# 02-MIC.net
KiCad netlist of a schematic drawn in Altium Designer
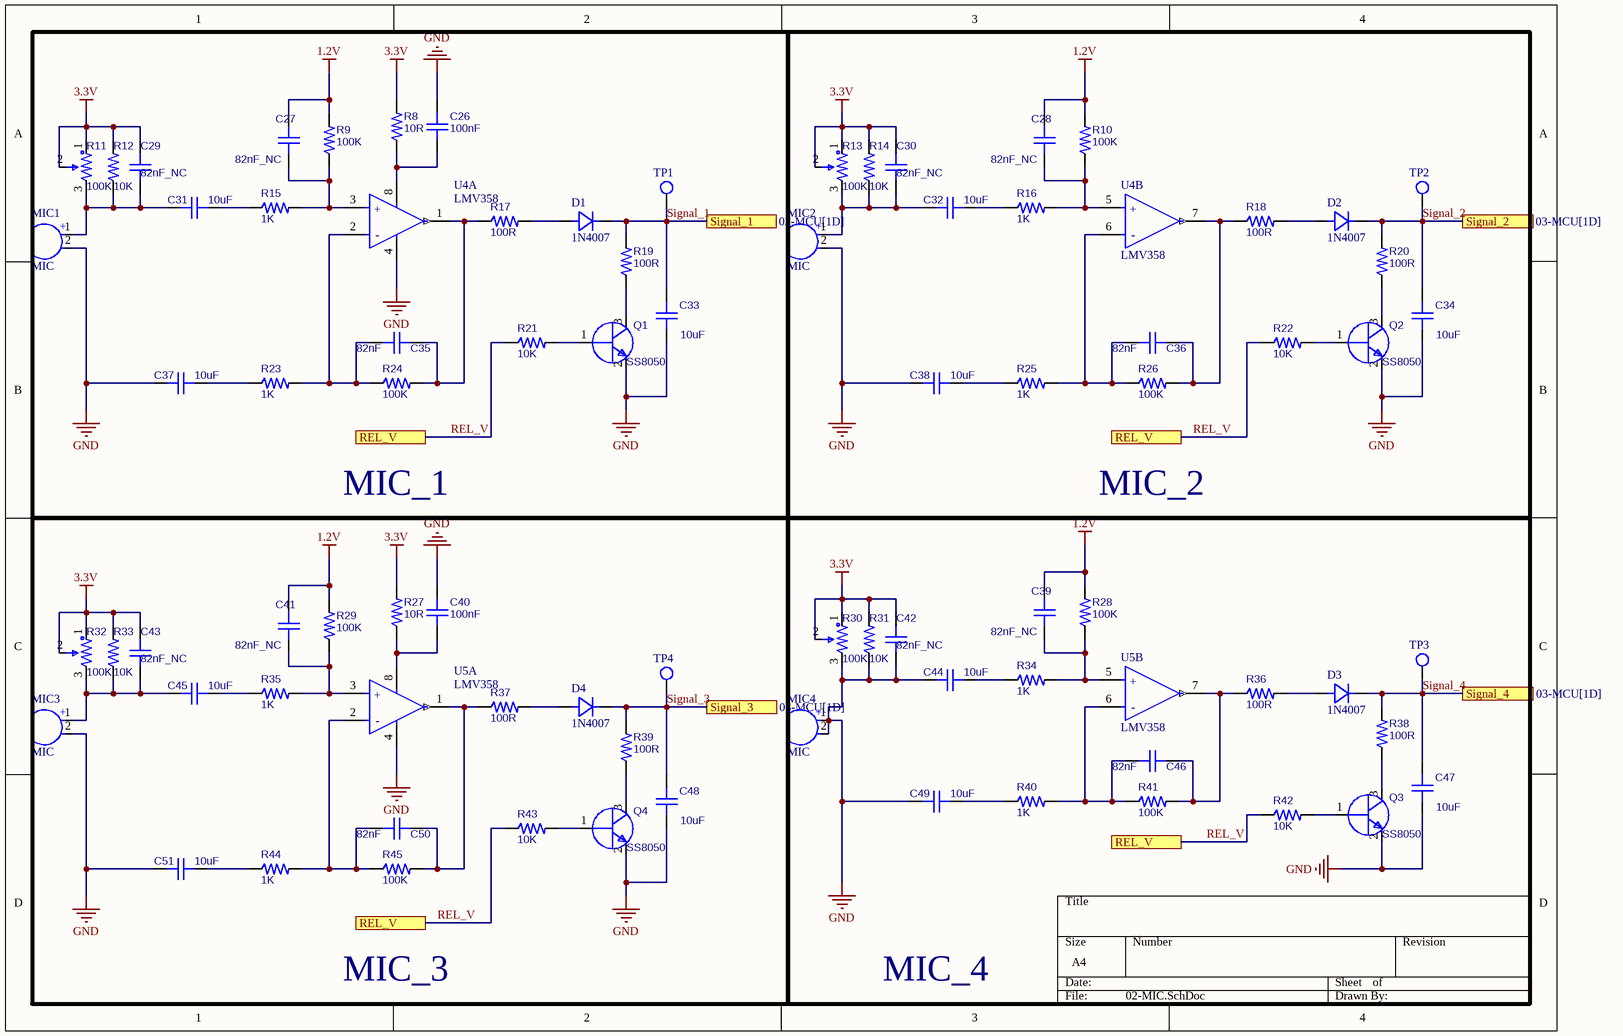
[diagram p0: 02-MIC.SchDoc]

(export (version "E")
  (design (tool "Eeschema 10.0.6"))
  (components
    (comp (ref "C26")
      (value "100nF")
      (footprint "CAP-SMD-0603")
      (description "贴片电容")
      (fields
        (field (name "BOM_MANUFACTURER PART") "CL03A104KQ3NNNC")
        (field (name "BOM_SUPPLIER PART") "C160831")
        (field (name "CONTRIBUTOR") "LCSC")
      )
      (libsource (lib "声源跟踪小车原理图库") (part "CAP"))
    )
    (comp (ref "C27")
      (value "82nF_NC")
      (footprint "CAP-SMD-0603")
      (description "贴片电容")
      (fields
        (field (name "BOM_MANUFACTURER PART") "CL03A104KQ3NNNC")
        (field (name "BOM_SUPPLIER PART") "C160831")
        (field (name "CONTRIBUTOR") "LCSC")
      )
      (libsource (lib "声源跟踪小车原理图库") (part "CAP"))
    )
    (comp (ref "C28")
      (value "82nF_NC")
      (footprint "CAP-SMD-0603")
      (description "贴片电容")
      (fields
        (field (name "BOM_MANUFACTURER PART") "CL03A104KQ3NNNC")
        (field (name "BOM_SUPPLIER PART") "C160831")
        (field (name "CONTRIBUTOR") "LCSC")
      )
      (libsource (lib "声源跟踪小车原理图库") (part "CAP"))
    )
    (comp (ref "C29")
      (value "82nF_NC")
      (footprint "CAP-SMD-0603")
      (description "贴片电容")
      (fields
        (field (name "BOM_MANUFACTURER PART") "CL03A104KQ3NNNC")
        (field (name "BOM_SUPPLIER PART") "C160831")
        (field (name "CONTRIBUTOR") "LCSC")
      )
      (libsource (lib "声源跟踪小车原理图库") (part "CAP"))
    )
    (comp (ref "C30")
      (value "82nF_NC")
      (footprint "CAP-SMD-0603")
      (description "贴片电容")
      (fields
        (field (name "BOM_MANUFACTURER PART") "CL03A104KQ3NNNC")
        (field (name "BOM_SUPPLIER PART") "C160831")
        (field (name "CONTRIBUTOR") "LCSC")
      )
      (libsource (lib "声源跟踪小车原理图库") (part "CAP"))
    )
    (comp (ref "C31")
      (value "10uF")
      (footprint "CAP-SMD-0603")
      (description "贴片电容")
      (fields
        (field (name "BOM_MANUFACTURER PART") "CL03A104KQ3NNNC")
        (field (name "BOM_SUPPLIER PART") "C160831")
        (field (name "CONTRIBUTOR") "LCSC")
      )
      (libsource (lib "声源跟踪小车原理图库") (part "CAP"))
    )
    (comp (ref "C32")
      (value "10uF")
      (footprint "CAP-SMD-0603")
      (description "贴片电容")
      (fields
        (field (name "BOM_MANUFACTURER PART") "CL03A104KQ3NNNC")
        (field (name "BOM_SUPPLIER PART") "C160831")
        (field (name "CONTRIBUTOR") "LCSC")
      )
      (libsource (lib "声源跟踪小车原理图库") (part "CAP"))
    )
    (comp (ref "C33")
      (value "10uF")
      (footprint "CAP-SMD-0603")
      (description "贴片电容")
      (fields
        (field (name "BOM_MANUFACTURER PART") "CL03A104KQ3NNNC")
        (field (name "BOM_SUPPLIER PART") "C160831")
        (field (name "CONTRIBUTOR") "LCSC")
      )
      (libsource (lib "声源跟踪小车原理图库") (part "CAP"))
    )
    (comp (ref "C34")
      (value "10uF")
      (footprint "CAP-SMD-0603")
      (description "贴片电容")
      (fields
        (field (name "BOM_MANUFACTURER PART") "CL03A104KQ3NNNC")
        (field (name "BOM_SUPPLIER PART") "C160831")
        (field (name "CONTRIBUTOR") "LCSC")
      )
      (libsource (lib "声源跟踪小车原理图库") (part "CAP"))
    )
    (comp (ref "C35")
      (value "82nF")
      (footprint "CAP-SMD-0603")
      (description "贴片电容")
      (fields
        (field (name "BOM_MANUFACTURER PART") "CL03A104KQ3NNNC")
        (field (name "BOM_SUPPLIER PART") "C160831")
        (field (name "CONTRIBUTOR") "LCSC")
      )
      (libsource (lib "声源跟踪小车原理图库") (part "CAP"))
    )
    (comp (ref "C36")
      (value "82nF")
      (footprint "CAP-SMD-0603")
      (description "贴片电容")
      (fields
        (field (name "BOM_MANUFACTURER PART") "CL03A104KQ3NNNC")
        (field (name "BOM_SUPPLIER PART") "C160831")
        (field (name "CONTRIBUTOR") "LCSC")
      )
      (libsource (lib "声源跟踪小车原理图库") (part "CAP"))
    )
    (comp (ref "C37")
      (value "10uF")
      (footprint "CAP-SMD-0603")
      (description "贴片电容")
      (fields
        (field (name "BOM_MANUFACTURER PART") "CL03A104KQ3NNNC")
        (field (name "BOM_SUPPLIER PART") "C160831")
        (field (name "CONTRIBUTOR") "LCSC")
      )
      (libsource (lib "声源跟踪小车原理图库") (part "CAP"))
    )
    (comp (ref "C38")
      (value "10uF")
      (footprint "CAP-SMD-0603")
      (description "贴片电容")
      (fields
        (field (name "BOM_MANUFACTURER PART") "CL03A104KQ3NNNC")
        (field (name "BOM_SUPPLIER PART") "C160831")
        (field (name "CONTRIBUTOR") "LCSC")
      )
      (libsource (lib "声源跟踪小车原理图库") (part "CAP"))
    )
    (comp (ref "C39")
      (value "82nF_NC")
      (footprint "CAP-SMD-0603")
      (description "贴片电容")
      (fields
        (field (name "BOM_MANUFACTURER PART") "CL03A104KQ3NNNC")
        (field (name "BOM_SUPPLIER PART") "C160831")
        (field (name "CONTRIBUTOR") "LCSC")
      )
      (libsource (lib "声源跟踪小车原理图库") (part "CAP"))
    )
    (comp (ref "C40")
      (value "100nF")
      (footprint "CAP-SMD-0603")
      (description "贴片电容")
      (fields
        (field (name "BOM_MANUFACTURER PART") "CL03A104KQ3NNNC")
        (field (name "BOM_SUPPLIER PART") "C160831")
        (field (name "CONTRIBUTOR") "LCSC")
      )
      (libsource (lib "声源跟踪小车原理图库") (part "CAP"))
    )
    (comp (ref "C41")
      (value "82nF_NC")
      (footprint "CAP-SMD-0603")
      (description "贴片电容")
      (fields
        (field (name "BOM_MANUFACTURER PART") "CL03A104KQ3NNNC")
        (field (name "BOM_SUPPLIER PART") "C160831")
        (field (name "CONTRIBUTOR") "LCSC")
      )
      (libsource (lib "声源跟踪小车原理图库") (part "CAP"))
    )
    (comp (ref "C42")
      (value "82nF_NC")
      (footprint "CAP-SMD-0603")
      (description "贴片电容")
      (fields
        (field (name "BOM_MANUFACTURER PART") "CL03A104KQ3NNNC")
        (field (name "BOM_SUPPLIER PART") "C160831")
        (field (name "CONTRIBUTOR") "LCSC")
      )
      (libsource (lib "声源跟踪小车原理图库") (part "CAP"))
    )
    (comp (ref "C43")
      (value "82nF_NC")
      (footprint "CAP-SMD-0603")
      (description "贴片电容")
      (fields
        (field (name "BOM_MANUFACTURER PART") "CL03A104KQ3NNNC")
        (field (name "BOM_SUPPLIER PART") "C160831")
        (field (name "CONTRIBUTOR") "LCSC")
      )
      (libsource (lib "声源跟踪小车原理图库") (part "CAP"))
    )
    (comp (ref "C44")
      (value "10uF")
      (footprint "CAP-SMD-0603")
      (description "贴片电容")
      (fields
        (field (name "BOM_MANUFACTURER PART") "CL03A104KQ3NNNC")
        (field (name "BOM_SUPPLIER PART") "C160831")
        (field (name "CONTRIBUTOR") "LCSC")
      )
      (libsource (lib "声源跟踪小车原理图库") (part "CAP"))
    )
    (comp (ref "C45")
      (value "10uF")
      (footprint "CAP-SMD-0603")
      (description "贴片电容")
      (fields
        (field (name "BOM_MANUFACTURER PART") "CL03A104KQ3NNNC")
        (field (name "BOM_SUPPLIER PART") "C160831")
        (field (name "CONTRIBUTOR") "LCSC")
      )
      (libsource (lib "声源跟踪小车原理图库") (part "CAP"))
    )
    (comp (ref "C46")
      (value "82nF")
      (footprint "CAP-SMD-0603")
      (description "贴片电容")
      (fields
        (field (name "BOM_MANUFACTURER PART") "CL03A104KQ3NNNC")
        (field (name "BOM_SUPPLIER PART") "C160831")
        (field (name "CONTRIBUTOR") "LCSC")
      )
      (libsource (lib "声源跟踪小车原理图库") (part "CAP"))
    )
    (comp (ref "C47")
      (value "10uF")
      (footprint "CAP-SMD-0603")
      (description "贴片电容")
      (fields
        (field (name "BOM_MANUFACTURER PART") "CL03A104KQ3NNNC")
        (field (name "BOM_SUPPLIER PART") "C160831")
        (field (name "CONTRIBUTOR") "LCSC")
      )
      (libsource (lib "声源跟踪小车原理图库") (part "CAP"))
    )
    (comp (ref "C48")
      (value "10uF")
      (footprint "CAP-SMD-0603")
      (description "贴片电容")
      (fields
        (field (name "BOM_MANUFACTURER PART") "CL03A104KQ3NNNC")
        (field (name "BOM_SUPPLIER PART") "C160831")
        (field (name "CONTRIBUTOR") "LCSC")
      )
      (libsource (lib "声源跟踪小车原理图库") (part "CAP"))
    )
    (comp (ref "C49")
      (value "10uF")
      (footprint "CAP-SMD-0603")
      (description "贴片电容")
      (fields
        (field (name "BOM_MANUFACTURER PART") "CL03A104KQ3NNNC")
        (field (name "BOM_SUPPLIER PART") "C160831")
        (field (name "CONTRIBUTOR") "LCSC")
      )
      (libsource (lib "声源跟踪小车原理图库") (part "CAP"))
    )
    (comp (ref "C50")
      (value "82nF")
      (footprint "CAP-SMD-0603")
      (description "贴片电容")
      (fields
        (field (name "BOM_MANUFACTURER PART") "CL03A104KQ3NNNC")
        (field (name "BOM_SUPPLIER PART") "C160831")
        (field (name "CONTRIBUTOR") "LCSC")
      )
      (libsource (lib "声源跟踪小车原理图库") (part "CAP"))
    )
    (comp (ref "C51")
      (value "10uF")
      (footprint "CAP-SMD-0603")
      (description "贴片电容")
      (fields
        (field (name "BOM_MANUFACTURER PART") "CL03A104KQ3NNNC")
        (field (name "BOM_SUPPLIER PART") "C160831")
        (field (name "CONTRIBUTOR") "LCSC")
      )
      (libsource (lib "声源跟踪小车原理图库") (part "CAP"))
    )
    (comp (ref "D1")
      (value "1N4007")
      (footprint "SOD-123-P3.4")
      (description "二极管1N4148W")
      (fields (field (name "MANUFACTURER") "PSI(宝力芯)") (field (name "MANUFACTURER PART") "1N4148W"))
      (libsource (lib "声源跟踪小车原理图库") (part "Diode"))
    )
    (comp (ref "D2")
      (value "1N4007")
      (footprint "SOD-123-P3.4")
      (description "二极管1N4148W")
      (fields (field (name "MANUFACTURER") "PSI(宝力芯)") (field (name "MANUFACTURER PART") "1N4148W"))
      (libsource (lib "声源跟踪小车原理图库") (part "Diode"))
    )
    (comp (ref "D3")
      (value "1N4007")
      (footprint "SOD-123-P3.4")
      (description "二极管1N4148W")
      (fields (field (name "MANUFACTURER") "PSI(宝力芯)") (field (name "MANUFACTURER PART") "1N4148W"))
      (libsource (lib "声源跟踪小车原理图库") (part "Diode"))
    )
    (comp (ref "D4")
      (value "1N4007")
      (footprint "SOD-123-P3.4")
      (description "二极管1N4148W")
      (fields (field (name "MANUFACTURER") "PSI(宝力芯)") (field (name "MANUFACTURER PART") "1N4148W"))
      (libsource (lib "声源跟踪小车原理图库") (part "Diode"))
    )
    (comp (ref "MIC1")
      (value "MIC")
      (footprint "CONN-TH-1X2P-P2.54_2")
      (description "咪头MIC COND ANALOG OMNI -38DB")
      (libsource (lib "声源跟踪小车原理图库") (part "MIC"))
    )
    (comp (ref "MIC2")
      (value "MIC")
      (footprint "CONN-TH-1X2P-P2.54_2")
      (description "咪头MIC COND ANALOG OMNI -38DB")
      (libsource (lib "声源跟踪小车原理图库") (part "MIC"))
    )
    (comp (ref "MIC3")
      (value "MIC")
      (footprint "CONN-TH-1X2P-P2.54_2")
      (description "咪头MIC COND ANALOG OMNI -38DB")
      (libsource (lib "声源跟踪小车原理图库") (part "MIC"))
    )
    (comp (ref "MIC4")
      (value "MIC")
      (footprint "CONN-TH-1X2P-P2.54_2")
      (description "咪头MIC COND ANALOG OMNI -38DB")
      (libsource (lib "声源跟踪小车原理图库") (part "MIC"))
    )
    (comp (ref "Q1")
      (value "SS8050")
      (footprint "SOT-23-3-LP2.28-P1.91")
      (description "贴片NPN三极管")
      (fields
        (field (name "BOM_SUPPLIER PART") "C2898668")
        (field (name "BOM_MANUFACTURER PART") "S9013")
        (field (name "CONTRIBUTOR") "LCSC")
      )
      (libsource (lib "声源跟踪小车原理图库") (part "NPN-SOT-23-3"))
    )
    (comp (ref "Q2")
      (value "SS8050")
      (footprint "SOT-23-3-LP2.28-P1.91")
      (description "贴片NPN三极管")
      (fields
        (field (name "BOM_SUPPLIER PART") "C2898668")
        (field (name "BOM_MANUFACTURER PART") "S9013")
        (field (name "CONTRIBUTOR") "LCSC")
      )
      (libsource (lib "声源跟踪小车原理图库") (part "NPN-SOT-23-3"))
    )
    (comp (ref "Q3")
      (value "SS8050")
      (footprint "SOT-23-3-LP2.28-P1.91")
      (description "贴片NPN三极管")
      (fields
        (field (name "BOM_SUPPLIER PART") "C2898668")
        (field (name "BOM_MANUFACTURER PART") "S9013")
        (field (name "CONTRIBUTOR") "LCSC")
      )
      (libsource (lib "声源跟踪小车原理图库") (part "NPN-SOT-23-3"))
    )
    (comp (ref "Q4")
      (value "SS8050")
      (footprint "SOT-23-3-LP2.28-P1.91")
      (description "贴片NPN三极管")
      (fields
        (field (name "BOM_SUPPLIER PART") "C2898668")
        (field (name "BOM_MANUFACTURER PART") "S9013")
        (field (name "CONTRIBUTOR") "LCSC")
      )
      (libsource (lib "声源跟踪小车原理图库") (part "NPN-SOT-23-3"))
    )
    (comp (ref "R8")
      (value "10R")
      (footprint "RES-SMD-0603")
      (description "贴片电阻")
      (fields
        (field (name "BOM_SUPPLIER PART") "C118966")
        (field (name "BOM_MANUFACTURER PART") "3362P-1-104")
        (field (name "CONTRIBUTOR") "LCSC")
      )
      (libsource (lib "声源跟踪小车原理图库") (part "RES"))
    )
    (comp (ref "R9")
      (value "100K")
      (footprint "RES-SMD-0603")
      (description "贴片电阻")
      (fields
        (field (name "BOM_SUPPLIER PART") "C118966")
        (field (name "BOM_MANUFACTURER PART") "3362P-1-104")
        (field (name "CONTRIBUTOR") "LCSC")
      )
      (libsource (lib "声源跟踪小车原理图库") (part "RES"))
    )
    (comp (ref "R10")
      (value "100K")
      (footprint "RES-SMD-0603")
      (description "贴片电阻")
      (fields
        (field (name "BOM_SUPPLIER PART") "C118966")
        (field (name "BOM_MANUFACTURER PART") "3362P-1-104")
        (field (name "CONTRIBUTOR") "LCSC")
      )
      (libsource (lib "声源跟踪小车原理图库") (part "RES"))
    )
    (comp (ref "R11")
      (value "100K")
      (footprint "RES-TH-ADJ-3396W")
      (description "可调电阻,电位器")
      (fields
        (field (name "BOM_SUPPLIER PART") "C118966")
        (field (name "BOM_MANUFACTURER PART") "3362P-1-104")
        (field (name "CONTRIBUTOR") "LCSC")
      )
      (libsource (lib "声源跟踪小车原理图库") (part "RES-ADJ"))
    )
    (comp (ref "R12")
      (value "10K")
      (footprint "RES-SMD-0603")
      (description "贴片电阻")
      (fields
        (field (name "BOM_SUPPLIER PART") "C118966")
        (field (name "BOM_MANUFACTURER PART") "3362P-1-104")
        (field (name "CONTRIBUTOR") "LCSC")
      )
      (libsource (lib "声源跟踪小车原理图库") (part "RES"))
    )
    (comp (ref "R13")
      (value "100K")
      (footprint "RES-TH-ADJ-3396W")
      (description "可调电阻,电位器")
      (fields
        (field (name "BOM_SUPPLIER PART") "C118966")
        (field (name "BOM_MANUFACTURER PART") "3362P-1-104")
        (field (name "CONTRIBUTOR") "LCSC")
      )
      (libsource (lib "声源跟踪小车原理图库") (part "RES-ADJ"))
    )
    (comp (ref "R14")
      (value "10K")
      (footprint "RES-SMD-0603")
      (description "贴片电阻")
      (fields
        (field (name "BOM_SUPPLIER PART") "C118966")
        (field (name "BOM_MANUFACTURER PART") "3362P-1-104")
        (field (name "CONTRIBUTOR") "LCSC")
      )
      (libsource (lib "声源跟踪小车原理图库") (part "RES"))
    )
    (comp (ref "R15")
      (value "1K")
      (footprint "RES-SMD-0603")
      (description "贴片电阻")
      (fields
        (field (name "BOM_SUPPLIER PART") "C118966")
        (field (name "BOM_MANUFACTURER PART") "3362P-1-104")
        (field (name "CONTRIBUTOR") "LCSC")
      )
      (libsource (lib "声源跟踪小车原理图库") (part "RES"))
    )
    (comp (ref "R16")
      (value "1K")
      (footprint "RES-SMD-0603")
      (description "贴片电阻")
      (fields
        (field (name "BOM_SUPPLIER PART") "C118966")
        (field (name "BOM_MANUFACTURER PART") "3362P-1-104")
        (field (name "CONTRIBUTOR") "LCSC")
      )
      (libsource (lib "声源跟踪小车原理图库") (part "RES"))
    )
    (comp (ref "R17")
      (value "100R")
      (footprint "RES-SMD-0603")
      (description "贴片电阻")
      (fields
        (field (name "BOM_SUPPLIER PART") "C118966")
        (field (name "BOM_MANUFACTURER PART") "3362P-1-104")
        (field (name "CONTRIBUTOR") "LCSC")
      )
      (libsource (lib "声源跟踪小车原理图库") (part "RES"))
    )
    (comp (ref "R18")
      (value "100R")
      (footprint "RES-SMD-0603")
      (description "贴片电阻")
      (fields
        (field (name "BOM_SUPPLIER PART") "C118966")
        (field (name "BOM_MANUFACTURER PART") "3362P-1-104")
        (field (name "CONTRIBUTOR") "LCSC")
      )
      (libsource (lib "声源跟踪小车原理图库") (part "RES"))
    )
    (comp (ref "R19")
      (value "100R")
      (footprint "RES-SMD-0603")
      (description "贴片电阻")
      (fields
        (field (name "BOM_SUPPLIER PART") "C118966")
        (field (name "BOM_MANUFACTURER PART") "3362P-1-104")
        (field (name "CONTRIBUTOR") "LCSC")
      )
      (libsource (lib "声源跟踪小车原理图库") (part "RES"))
    )
    (comp (ref "R20")
      (value "100R")
      (footprint "RES-SMD-0603")
      (description "贴片电阻")
      (fields
        (field (name "BOM_SUPPLIER PART") "C118966")
        (field (name "BOM_MANUFACTURER PART") "3362P-1-104")
        (field (name "CONTRIBUTOR") "LCSC")
      )
      (libsource (lib "声源跟踪小车原理图库") (part "RES"))
    )
    (comp (ref "R21")
      (value "10K")
      (footprint "RES-SMD-0603")
      (description "贴片电阻")
      (fields
        (field (name "BOM_SUPPLIER PART") "C118966")
        (field (name "BOM_MANUFACTURER PART") "3362P-1-104")
        (field (name "CONTRIBUTOR") "LCSC")
      )
      (libsource (lib "声源跟踪小车原理图库") (part "RES"))
    )
    (comp (ref "R22")
      (value "10K")
      (footprint "RES-SMD-0603")
      (description "贴片电阻")
      (fields
        (field (name "BOM_SUPPLIER PART") "C118966")
        (field (name "BOM_MANUFACTURER PART") "3362P-1-104")
        (field (name "CONTRIBUTOR") "LCSC")
      )
      (libsource (lib "声源跟踪小车原理图库") (part "RES"))
    )
    (comp (ref "R23")
      (value "1K")
      (footprint "RES-SMD-0603")
      (description "贴片电阻")
      (fields
        (field (name "BOM_SUPPLIER PART") "C118966")
        (field (name "BOM_MANUFACTURER PART") "3362P-1-104")
        (field (name "CONTRIBUTOR") "LCSC")
      )
      (libsource (lib "声源跟踪小车原理图库") (part "RES"))
    )
    (comp (ref "R24")
      (value "100K")
      (footprint "RES-SMD-0603")
      (description "贴片电阻")
      (fields
        (field (name "BOM_SUPPLIER PART") "C118966")
        (field (name "BOM_MANUFACTURER PART") "3362P-1-104")
        (field (name "CONTRIBUTOR") "LCSC")
      )
      (libsource (lib "声源跟踪小车原理图库") (part "RES"))
    )
    (comp (ref "R25")
      (value "1K")
      (footprint "RES-SMD-0603")
      (description "贴片电阻")
      (fields
        (field (name "BOM_SUPPLIER PART") "C118966")
        (field (name "BOM_MANUFACTURER PART") "3362P-1-104")
        (field (name "CONTRIBUTOR") "LCSC")
      )
      (libsource (lib "声源跟踪小车原理图库") (part "RES"))
    )
    (comp (ref "R26")
      (value "100K")
      (footprint "RES-SMD-0603")
      (description "贴片电阻")
      (fields
        (field (name "BOM_SUPPLIER PART") "C118966")
        (field (name "BOM_MANUFACTURER PART") "3362P-1-104")
        (field (name "CONTRIBUTOR") "LCSC")
      )
      (libsource (lib "声源跟踪小车原理图库") (part "RES"))
    )
    (comp (ref "R27")
      (value "10R")
      (footprint "RES-SMD-0603")
      (description "贴片电阻")
      (fields
        (field (name "BOM_SUPPLIER PART") "C118966")
        (field (name "BOM_MANUFACTURER PART") "3362P-1-104")
        (field (name "CONTRIBUTOR") "LCSC")
      )
      (libsource (lib "声源跟踪小车原理图库") (part "RES"))
    )
    (comp (ref "R28")
      (value "100K")
      (footprint "RES-SMD-0603")
      (description "贴片电阻")
      (fields
        (field (name "BOM_SUPPLIER PART") "C118966")
        (field (name "BOM_MANUFACTURER PART") "3362P-1-104")
        (field (name "CONTRIBUTOR") "LCSC")
      )
      (libsource (lib "声源跟踪小车原理图库") (part "RES"))
    )
    (comp (ref "R29")
      (value "100K")
      (footprint "RES-SMD-0603")
      (description "贴片电阻")
      (fields
        (field (name "BOM_SUPPLIER PART") "C118966")
        (field (name "BOM_MANUFACTURER PART") "3362P-1-104")
        (field (name "CONTRIBUTOR") "LCSC")
      )
      (libsource (lib "声源跟踪小车原理图库") (part "RES"))
    )
    (comp (ref "R30")
      (value "100K")
      (footprint "RES-TH-ADJ-3396W")
      (description "可调电阻,电位器")
      (fields
        (field (name "BOM_SUPPLIER PART") "C118966")
        (field (name "BOM_MANUFACTURER PART") "3362P-1-104")
        (field (name "CONTRIBUTOR") "LCSC")
      )
      (libsource (lib "声源跟踪小车原理图库") (part "RES-ADJ"))
    )
    (comp (ref "R31")
      (value "10K")
      (footprint "RES-SMD-0603")
      (description "贴片电阻")
      (fields
        (field (name "BOM_SUPPLIER PART") "C118966")
        (field (name "BOM_MANUFACTURER PART") "3362P-1-104")
        (field (name "CONTRIBUTOR") "LCSC")
      )
      (libsource (lib "声源跟踪小车原理图库") (part "RES"))
    )
    (comp (ref "R32")
      (value "100K")
      (footprint "RES-TH-ADJ-3396W")
      (description "可调电阻,电位器")
      (fields
        (field (name "BOM_SUPPLIER PART") "C118966")
        (field (name "BOM_MANUFACTURER PART") "3362P-1-104")
        (field (name "CONTRIBUTOR") "LCSC")
      )
      (libsource (lib "声源跟踪小车原理图库") (part "RES-ADJ"))
    )
    (comp (ref "R33")
      (value "10K")
      (footprint "RES-SMD-0603")
      (description "贴片电阻")
      (fields
        (field (name "BOM_SUPPLIER PART") "C118966")
        (field (name "BOM_MANUFACTURER PART") "3362P-1-104")
        (field (name "CONTRIBUTOR") "LCSC")
      )
      (libsource (lib "声源跟踪小车原理图库") (part "RES"))
    )
    (comp (ref "R34")
      (value "1K")
      (footprint "RES-SMD-0603")
      (description "贴片电阻")
      (fields
        (field (name "BOM_SUPPLIER PART") "C118966")
        (field (name "BOM_MANUFACTURER PART") "3362P-1-104")
        (field (name "CONTRIBUTOR") "LCSC")
      )
      (libsource (lib "声源跟踪小车原理图库") (part "RES"))
    )
    (comp (ref "R35")
      (value "1K")
      (footprint "RES-SMD-0603")
      (description "贴片电阻")
      (fields
        (field (name "BOM_SUPPLIER PART") "C118966")
        (field (name "BOM_MANUFACTURER PART") "3362P-1-104")
        (field (name "CONTRIBUTOR") "LCSC")
      )
      (libsource (lib "声源跟踪小车原理图库") (part "RES"))
    )
    (comp (ref "R36")
      (value "100R")
      (footprint "RES-SMD-0603")
      (description "贴片电阻")
      (fields
        (field (name "BOM_SUPPLIER PART") "C118966")
        (field (name "BOM_MANUFACTURER PART") "3362P-1-104")
        (field (name "CONTRIBUTOR") "LCSC")
      )
      (libsource (lib "声源跟踪小车原理图库") (part "RES"))
    )
    (comp (ref "R37")
      (value "100R")
      (footprint "RES-SMD-0603")
      (description "贴片电阻")
      (fields
        (field (name "BOM_SUPPLIER PART") "C118966")
        (field (name "BOM_MANUFACTURER PART") "3362P-1-104")
        (field (name "CONTRIBUTOR") "LCSC")
      )
      (libsource (lib "声源跟踪小车原理图库") (part "RES"))
    )
    (comp (ref "R38")
      (value "100R")
      (footprint "RES-SMD-0603")
      (description "贴片电阻")
      (fields
        (field (name "BOM_SUPPLIER PART") "C118966")
        (field (name "BOM_MANUFACTURER PART") "3362P-1-104")
        (field (name "CONTRIBUTOR") "LCSC")
      )
      (libsource (lib "声源跟踪小车原理图库") (part "RES"))
    )
    (comp (ref "R39")
      (value "100R")
      (footprint "RES-SMD-0603")
      (description "贴片电阻")
      (fields
        (field (name "BOM_SUPPLIER PART") "C118966")
        (field (name "BOM_MANUFACTURER PART") "3362P-1-104")
        (field (name "CONTRIBUTOR") "LCSC")
      )
      (libsource (lib "声源跟踪小车原理图库") (part "RES"))
    )
    (comp (ref "R40")
      (value "1K")
      (footprint "RES-SMD-0603")
      (description "贴片电阻")
      (fields
        (field (name "BOM_SUPPLIER PART") "C118966")
        (field (name "BOM_MANUFACTURER PART") "3362P-1-104")
        (field (name "CONTRIBUTOR") "LCSC")
      )
      (libsource (lib "声源跟踪小车原理图库") (part "RES"))
    )
    (comp (ref "R41")
      (value "100K")
      (footprint "RES-SMD-0603")
      (description "贴片电阻")
      (fields
        (field (name "BOM_SUPPLIER PART") "C118966")
        (field (name "BOM_MANUFACTURER PART") "3362P-1-104")
        (field (name "CONTRIBUTOR") "LCSC")
      )
      (libsource (lib "声源跟踪小车原理图库") (part "RES"))
    )
    (comp (ref "R42")
      (value "10K")
      (footprint "RES-SMD-0603")
      (description "贴片电阻")
      (fields
        (field (name "BOM_SUPPLIER PART") "C118966")
        (field (name "BOM_MANUFACTURER PART") "3362P-1-104")
        (field (name "CONTRIBUTOR") "LCSC")
      )
      (libsource (lib "声源跟踪小车原理图库") (part "RES"))
    )
    (comp (ref "R43")
      (value "10K")
      (footprint "RES-SMD-0603")
      (description "贴片电阻")
      (fields
        (field (name "BOM_SUPPLIER PART") "C118966")
        (field (name "BOM_MANUFACTURER PART") "3362P-1-104")
        (field (name "CONTRIBUTOR") "LCSC")
      )
      (libsource (lib "声源跟踪小车原理图库") (part "RES"))
    )
    (comp (ref "R44")
      (value "1K")
      (footprint "RES-SMD-0603")
      (description "贴片电阻")
      (fields
        (field (name "BOM_SUPPLIER PART") "C118966")
        (field (name "BOM_MANUFACTURER PART") "3362P-1-104")
        (field (name "CONTRIBUTOR") "LCSC")
      )
      (libsource (lib "声源跟踪小车原理图库") (part "RES"))
    )
    (comp (ref "R45")
      (value "100K")
      (footprint "RES-SMD-0603")
      (description "贴片电阻")
      (fields
        (field (name "BOM_SUPPLIER PART") "C118966")
        (field (name "BOM_MANUFACTURER PART") "3362P-1-104")
        (field (name "CONTRIBUTOR") "LCSC")
      )
      (libsource (lib "声源跟踪小车原理图库") (part "RES"))
    )
    (comp (ref "TP1")
      (value "TP")
      (footprint "TP")
      (description "TP测试点")
      (libsource (lib "声源跟踪小车原理图库") (part "TP"))
    )
    (comp (ref "TP2")
      (value "TP")
      (footprint "TP")
      (description "TP测试点")
      (libsource (lib "声源跟踪小车原理图库") (part "TP"))
    )
    (comp (ref "TP3")
      (value "TP")
      (footprint "TP")
      (description "TP测试点")
      (libsource (lib "声源跟踪小车原理图库") (part "TP"))
    )
    (comp (ref "TP4")
      (value "TP")
      (footprint "TP")
      (description "TP测试点")
      (libsource (lib "声源跟踪小车原理图库") (part "TP"))
    )
    (comp (ref "U4")
      (value "LMV358")
      (footprint "SOIC-8-LP5.5-P1.27")
      (description "运放IC OPAMP GP 2 CIRCUIT 8SOIC")
      (libsource (lib "声源跟踪小车原理图库") (part "LMV358"))
    )
    (comp (ref "U5")
      (value "LMV358")
      (footprint "SOIC-8-LP5.5-P1.27")
      (description "运放IC OPAMP GP 2 CIRCUIT 8SOIC")
      (libsource (lib "声源跟踪小车原理图库") (part "LMV358"))
    )
  )
  (nets
    (net (code "1") (name "/REL_V") (class "Default")
      (node (ref "R21") (pin "1") (pinfunction "1_1") (pintype "passive"))
      (node (ref "R22") (pin "1") (pinfunction "1_1") (pintype "passive"))
      (node (ref "R42") (pin "1") (pinfunction "1_1") (pintype "passive"))
      (node (ref "R43") (pin "1") (pinfunction "1_1") (pintype "passive"))
    )
    (net (code "2") (name "/Signal_1") (class "Default")
      (node (ref "C33") (pin "2") (pinfunction "2_2") (pintype "passive"))
      (node (ref "D1") (pin "2") (pinfunction "A_2") (pintype "passive"))
      (node (ref "R19") (pin "2") (pinfunction "2_2") (pintype "passive"))
      (node (ref "TP1") (pin "1") (pinfunction "1_1") (pintype "passive"))
    )
    (net (code "3") (name "/Signal_2") (class "Default")
      (node (ref "C34") (pin "2") (pinfunction "2_2") (pintype "passive"))
      (node (ref "D2") (pin "2") (pinfunction "A_2") (pintype "passive"))
      (node (ref "R20") (pin "2") (pinfunction "2_2") (pintype "passive"))
      (node (ref "TP2") (pin "1") (pinfunction "1_1") (pintype "passive"))
    )
    (net (code "4") (name "/Signal_3") (class "Default")
      (node (ref "C48") (pin "2") (pinfunction "2_2") (pintype "passive"))
      (node (ref "D4") (pin "2") (pinfunction "A_2") (pintype "passive"))
      (node (ref "R39") (pin "2") (pinfunction "2_2") (pintype "passive"))
      (node (ref "TP4") (pin "1") (pinfunction "1_1") (pintype "passive"))
    )
    (net (code "5") (name "/Signal_4") (class "Default")
      (node (ref "C47") (pin "2") (pinfunction "2_2") (pintype "passive"))
      (node (ref "D3") (pin "2") (pinfunction "A_2") (pintype "passive"))
      (node (ref "R38") (pin "2") (pinfunction "2_2") (pintype "passive"))
      (node (ref "TP3") (pin "1") (pinfunction "1_1") (pintype "passive"))
    )
    (net (code "6") (name "1.2V") (class "Default")
      (node (ref "C27") (pin "2") (pinfunction "2_2") (pintype "passive"))
      (node (ref "C28") (pin "2") (pinfunction "2_2") (pintype "passive"))
      (node (ref "C39") (pin "2") (pinfunction "2_2") (pintype "passive"))
      (node (ref "C41") (pin "2") (pinfunction "2_2") (pintype "passive"))
      (node (ref "R10") (pin "2") (pinfunction "2_2") (pintype "passive"))
      (node (ref "R28") (pin "2") (pinfunction "2_2") (pintype "passive"))
      (node (ref "R29") (pin "2") (pinfunction "2_2") (pintype "passive"))
      (node (ref "R9") (pin "2") (pinfunction "2_2") (pintype "passive"))
    )
    (net (code "7") (name "3.3V") (class "Default")
      (node (ref "C29") (pin "2") (pinfunction "2_2") (pintype "passive"))
      (node (ref "C30") (pin "2") (pinfunction "2_2") (pintype "passive"))
      (node (ref "C42") (pin "2") (pinfunction "2_2") (pintype "passive"))
      (node (ref "C43") (pin "2") (pinfunction "2_2") (pintype "passive"))
      (node (ref "R11") (pin "1") (pinfunction "1_1") (pintype "passive"))
      (node (ref "R11") (pin "2") (pinfunction "2_2") (pintype "passive"))
      (node (ref "R12") (pin "2") (pinfunction "2_2") (pintype "passive"))
      (node (ref "R13") (pin "1") (pinfunction "1_1") (pintype "passive"))
      (node (ref "R13") (pin "2") (pinfunction "2_2") (pintype "passive"))
      (node (ref "R14") (pin "2") (pinfunction "2_2") (pintype "passive"))
      (node (ref "R27") (pin "2") (pinfunction "2_2") (pintype "passive"))
      (node (ref "R30") (pin "1") (pinfunction "1_1") (pintype "passive"))
      (node (ref "R30") (pin "2") (pinfunction "2_2") (pintype "passive"))
      (node (ref "R31") (pin "2") (pinfunction "2_2") (pintype "passive"))
      (node (ref "R32") (pin "1") (pinfunction "1_1") (pintype "passive"))
      (node (ref "R32") (pin "2") (pinfunction "2_2") (pintype "passive"))
      (node (ref "R33") (pin "2") (pinfunction "2_2") (pintype "passive"))
      (node (ref "R8") (pin "2") (pinfunction "2_2") (pintype "passive"))
    )
    (net (code "8") (name "GND") (class "Default")
      (node (ref "C26") (pin "2") (pinfunction "2_2") (pintype "passive"))
      (node (ref "C33") (pin "1") (pinfunction "1_1") (pintype "passive"))
      (node (ref "C34") (pin "1") (pinfunction "1_1") (pintype "passive"))
      (node (ref "C37") (pin "1") (pinfunction "1_1") (pintype "passive"))
      (node (ref "C38") (pin "1") (pinfunction "1_1") (pintype "passive"))
      (node (ref "C40") (pin "2") (pinfunction "2_2") (pintype "passive"))
      (node (ref "C42") (pin "1") (pinfunction "1_1") (pintype "passive"))
      (node (ref "C44") (pin "1") (pinfunction "1_1") (pintype "passive"))
      (node (ref "C47") (pin "1") (pinfunction "1_1") (pintype "passive"))
      (node (ref "C48") (pin "1") (pinfunction "1_1") (pintype "passive"))
      (node (ref "C49") (pin "1") (pinfunction "1_1") (pintype "passive"))
      (node (ref "C51") (pin "1") (pinfunction "1_1") (pintype "passive"))
      (node (ref "MIC1") (pin "2") (pinfunction "C_2") (pintype "passive"))
      (node (ref "MIC2") (pin "2") (pinfunction "C_2") (pintype "passive"))
      (node (ref "MIC3") (pin "2") (pinfunction "C_2") (pintype "passive"))
      (node (ref "MIC4") (pin "1") (pinfunction "A_1") (pintype "passive"))
      (node (ref "MIC4") (pin "2") (pinfunction "C_2") (pintype "passive"))
      (node (ref "Q1") (pin "2") (pinfunction "E_2") (pintype "passive"))
      (node (ref "Q2") (pin "2") (pinfunction "E_2") (pintype "passive"))
      (node (ref "Q3") (pin "2") (pinfunction "E_2") (pintype "passive"))
      (node (ref "Q4") (pin "2") (pinfunction "E_2") (pintype "passive"))
      (node (ref "R30") (pin "3") (pinfunction "3_3") (pintype "passive"))
      (node (ref "R31") (pin "1") (pinfunction "1_1") (pintype "passive"))
      (node (ref "U4") (pin "4") (pinfunction "GND_4") (pintype "power_in"))
      (node (ref "U5") (pin "4") (pinfunction "GND_4") (pintype "power_in"))
    )
    (net (code "9") (name "Net-(C31-Pad2)") (class "Default")
      (node (ref "C31") (pin "2") (pinfunction "2_2") (pintype "passive"))
      (node (ref "R15") (pin "1") (pinfunction "1_1") (pintype "passive"))
    )
    (net (code "10") (name "Net-(C32-Pad2)") (class "Default")
      (node (ref "C32") (pin "2") (pinfunction "2_2") (pintype "passive"))
      (node (ref "R16") (pin "1") (pinfunction "1_1") (pintype "passive"))
    )
    (net (code "11") (name "Net-(C37-Pad2)") (class "Default")
      (node (ref "C37") (pin "2") (pinfunction "2_2") (pintype "passive"))
      (node (ref "R23") (pin "1") (pinfunction "1_1") (pintype "passive"))
    )
    (net (code "12") (name "Net-(C38-Pad2)") (class "Default")
      (node (ref "C38") (pin "2") (pinfunction "2_2") (pintype "passive"))
      (node (ref "R25") (pin "1") (pinfunction "1_1") (pintype "passive"))
    )
    (net (code "13") (name "Net-(C44-Pad2)") (class "Default")
      (node (ref "C44") (pin "2") (pinfunction "2_2") (pintype "passive"))
      (node (ref "R34") (pin "1") (pinfunction "1_1") (pintype "passive"))
    )
    (net (code "14") (name "Net-(C45-Pad2)") (class "Default")
      (node (ref "C45") (pin "2") (pinfunction "2_2") (pintype "passive"))
      (node (ref "R35") (pin "1") (pinfunction "1_1") (pintype "passive"))
    )
    (net (code "15") (name "Net-(C49-Pad2)") (class "Default")
      (node (ref "C49") (pin "2") (pinfunction "2_2") (pintype "passive"))
      (node (ref "R40") (pin "1") (pinfunction "1_1") (pintype "passive"))
    )
    (net (code "16") (name "Net-(C51-Pad2)") (class "Default")
      (node (ref "C51") (pin "2") (pinfunction "2_2") (pintype "passive"))
      (node (ref "R44") (pin "1") (pinfunction "1_1") (pintype "passive"))
    )
    (net (code "17") (name "Net-(D1-K)") (class "Default")
      (node (ref "D1") (pin "1") (pinfunction "K_1") (pintype "passive"))
      (node (ref "R17") (pin "2") (pinfunction "2_2") (pintype "passive"))
    )
    (net (code "18") (name "Net-(D2-K)") (class "Default")
      (node (ref "D2") (pin "1") (pinfunction "K_1") (pintype "passive"))
      (node (ref "R18") (pin "2") (pinfunction "2_2") (pintype "passive"))
    )
    (net (code "19") (name "Net-(D3-K)") (class "Default")
      (node (ref "D3") (pin "1") (pinfunction "K_1") (pintype "passive"))
      (node (ref "R36") (pin "2") (pinfunction "2_2") (pintype "passive"))
    )
    (net (code "20") (name "Net-(D4-K)") (class "Default")
      (node (ref "D4") (pin "1") (pinfunction "K_1") (pintype "passive"))
      (node (ref "R37") (pin "2") (pinfunction "2_2") (pintype "passive"))
    )
    (net (code "21") (name "Net-(MIC1-A)") (class "Default")
      (node (ref "C29") (pin "1") (pinfunction "1_1") (pintype "passive"))
      (node (ref "C31") (pin "1") (pinfunction "1_1") (pintype "passive"))
      (node (ref "MIC1") (pin "1") (pinfunction "A_1") (pintype "passive"))
      (node (ref "R11") (pin "3") (pinfunction "3_3") (pintype "passive"))
      (node (ref "R12") (pin "1") (pinfunction "1_1") (pintype "passive"))
    )
    (net (code "22") (name "Net-(MIC2-A)") (class "Default")
      (node (ref "C30") (pin "1") (pinfunction "1_1") (pintype "passive"))
      (node (ref "C32") (pin "1") (pinfunction "1_1") (pintype "passive"))
      (node (ref "MIC2") (pin "1") (pinfunction "A_1") (pintype "passive"))
      (node (ref "R13") (pin "3") (pinfunction "3_3") (pintype "passive"))
      (node (ref "R14") (pin "1") (pinfunction "1_1") (pintype "passive"))
    )
    (net (code "23") (name "Net-(MIC3-A)") (class "Default")
      (node (ref "C43") (pin "1") (pinfunction "1_1") (pintype "passive"))
      (node (ref "C45") (pin "1") (pinfunction "1_1") (pintype "passive"))
      (node (ref "MIC3") (pin "1") (pinfunction "A_1") (pintype "passive"))
      (node (ref "R32") (pin "3") (pinfunction "3_3") (pintype "passive"))
      (node (ref "R33") (pin "1") (pinfunction "1_1") (pintype "passive"))
    )
    (net (code "24") (name "Net-(Q1-B)") (class "Default")
      (node (ref "Q1") (pin "1") (pinfunction "B_1") (pintype "passive"))
      (node (ref "R21") (pin "2") (pinfunction "2_2") (pintype "passive"))
    )
    (net (code "25") (name "Net-(Q1-C)") (class "Default")
      (node (ref "Q1") (pin "3") (pinfunction "C_3") (pintype "passive"))
      (node (ref "R19") (pin "1") (pinfunction "1_1") (pintype "passive"))
    )
    (net (code "26") (name "Net-(Q2-B)") (class "Default")
      (node (ref "Q2") (pin "1") (pinfunction "B_1") (pintype "passive"))
      (node (ref "R22") (pin "2") (pinfunction "2_2") (pintype "passive"))
    )
    (net (code "27") (name "Net-(Q2-C)") (class "Default")
      (node (ref "Q2") (pin "3") (pinfunction "C_3") (pintype "passive"))
      (node (ref "R20") (pin "1") (pinfunction "1_1") (pintype "passive"))
    )
    (net (code "28") (name "Net-(Q3-B)") (class "Default")
      (node (ref "Q3") (pin "1") (pinfunction "B_1") (pintype "passive"))
      (node (ref "R42") (pin "2") (pinfunction "2_2") (pintype "passive"))
    )
    (net (code "29") (name "Net-(Q3-C)") (class "Default")
      (node (ref "Q3") (pin "3") (pinfunction "C_3") (pintype "passive"))
      (node (ref "R38") (pin "1") (pinfunction "1_1") (pintype "passive"))
    )
    (net (code "30") (name "Net-(Q4-B)") (class "Default")
      (node (ref "Q4") (pin "1") (pinfunction "B_1") (pintype "passive"))
      (node (ref "R43") (pin "2") (pinfunction "2_2") (pintype "passive"))
    )
    (net (code "31") (name "Net-(Q4-C)") (class "Default")
      (node (ref "Q4") (pin "3") (pinfunction "C_3") (pintype "passive"))
      (node (ref "R39") (pin "1") (pinfunction "1_1") (pintype "passive"))
    )
    (net (code "32") (name "Net-(U4A-1IN+)") (class "Default")
      (node (ref "C27") (pin "1") (pinfunction "1_1") (pintype "passive"))
      (node (ref "R15") (pin "2") (pinfunction "2_2") (pintype "passive"))
      (node (ref "R9") (pin "1") (pinfunction "1_1") (pintype "passive"))
      (node (ref "U4") (pin "3") (pinfunction "1IN+_3") (pintype "tri_state"))
    )
    (net (code "33") (name "Net-(U4A-1IN-)") (class "Default")
      (node (ref "C35") (pin "1") (pinfunction "1_1") (pintype "passive"))
      (node (ref "R23") (pin "2") (pinfunction "2_2") (pintype "passive"))
      (node (ref "R24") (pin "1") (pinfunction "1_1") (pintype "passive"))
      (node (ref "U4") (pin "2") (pinfunction "1IN-_2") (pintype "tri_state"))
    )
    (net (code "34") (name "Net-(U4A-OUT)") (class "Default")
      (node (ref "C35") (pin "2") (pinfunction "2_2") (pintype "passive"))
      (node (ref "R17") (pin "1") (pinfunction "1_1") (pintype "passive"))
      (node (ref "R24") (pin "2") (pinfunction "2_2") (pintype "passive"))
      (node (ref "U4") (pin "1") (pinfunction "OUT_1") (pintype "output"))
    )
    (net (code "35") (name "Net-(U4A-VCC+)") (class "Default")
      (node (ref "C26") (pin "1") (pinfunction "1_1") (pintype "passive"))
      (node (ref "R8") (pin "1") (pinfunction "1_1") (pintype "passive"))
      (node (ref "U4") (pin "8") (pinfunction "VCC+_8") (pintype "power_in"))
    )
    (net (code "36") (name "Net-(U4B-1IN+)") (class "Default")
      (node (ref "C28") (pin "1") (pinfunction "1_1") (pintype "passive"))
      (node (ref "R10") (pin "1") (pinfunction "1_1") (pintype "passive"))
      (node (ref "R16") (pin "2") (pinfunction "2_2") (pintype "passive"))
      (node (ref "U4") (pin "5") (pinfunction "1IN+_5") (pintype "tri_state"))
    )
    (net (code "37") (name "Net-(U4B-1IN-)") (class "Default")
      (node (ref "C36") (pin "1") (pinfunction "1_1") (pintype "passive"))
      (node (ref "R25") (pin "2") (pinfunction "2_2") (pintype "passive"))
      (node (ref "R26") (pin "1") (pinfunction "1_1") (pintype "passive"))
      (node (ref "U4") (pin "6") (pinfunction "1IN-_6") (pintype "tri_state"))
    )
    (net (code "38") (name "Net-(U4B-OUT)") (class "Default")
      (node (ref "C36") (pin "2") (pinfunction "2_2") (pintype "passive"))
      (node (ref "R18") (pin "1") (pinfunction "1_1") (pintype "passive"))
      (node (ref "R26") (pin "2") (pinfunction "2_2") (pintype "passive"))
      (node (ref "U4") (pin "7") (pinfunction "OUT_7") (pintype "output"))
    )
    (net (code "39") (name "Net-(U5A-1IN+)") (class "Default")
      (node (ref "C41") (pin "1") (pinfunction "1_1") (pintype "passive"))
      (node (ref "R29") (pin "1") (pinfunction "1_1") (pintype "passive"))
      (node (ref "R35") (pin "2") (pinfunction "2_2") (pintype "passive"))
      (node (ref "U5") (pin "3") (pinfunction "1IN+_3") (pintype "tri_state"))
    )
    (net (code "40") (name "Net-(U5A-1IN-)") (class "Default")
      (node (ref "C50") (pin "1") (pinfunction "1_1") (pintype "passive"))
      (node (ref "R44") (pin "2") (pinfunction "2_2") (pintype "passive"))
      (node (ref "R45") (pin "1") (pinfunction "1_1") (pintype "passive"))
      (node (ref "U5") (pin "2") (pinfunction "1IN-_2") (pintype "tri_state"))
    )
    (net (code "41") (name "Net-(U5A-OUT)") (class "Default")
      (node (ref "C50") (pin "2") (pinfunction "2_2") (pintype "passive"))
      (node (ref "R37") (pin "1") (pinfunction "1_1") (pintype "passive"))
      (node (ref "R45") (pin "2") (pinfunction "2_2") (pintype "passive"))
      (node (ref "U5") (pin "1") (pinfunction "OUT_1") (pintype "output"))
    )
    (net (code "42") (name "Net-(U5A-VCC+)") (class "Default")
      (node (ref "C40") (pin "1") (pinfunction "1_1") (pintype "passive"))
      (node (ref "R27") (pin "1") (pinfunction "1_1") (pintype "passive"))
      (node (ref "U5") (pin "8") (pinfunction "VCC+_8") (pintype "power_in"))
    )
    (net (code "43") (name "Net-(U5B-1IN+)") (class "Default")
      (node (ref "C39") (pin "1") (pinfunction "1_1") (pintype "passive"))
      (node (ref "R28") (pin "1") (pinfunction "1_1") (pintype "passive"))
      (node (ref "R34") (pin "2") (pinfunction "2_2") (pintype "passive"))
      (node (ref "U5") (pin "5") (pinfunction "1IN+_5") (pintype "tri_state"))
    )
    (net (code "44") (name "Net-(U5B-1IN-)") (class "Default")
      (node (ref "C46") (pin "1") (pinfunction "1_1") (pintype "passive"))
      (node (ref "R40") (pin "2") (pinfunction "2_2") (pintype "passive"))
      (node (ref "R41") (pin "1") (pinfunction "1_1") (pintype "passive"))
      (node (ref "U5") (pin "6") (pinfunction "1IN-_6") (pintype "tri_state"))
    )
    (net (code "45") (name "Net-(U5B-OUT)") (class "Default")
      (node (ref "C46") (pin "2") (pinfunction "2_2") (pintype "passive"))
      (node (ref "R36") (pin "1") (pinfunction "1_1") (pintype "passive"))
      (node (ref "R41") (pin "2") (pinfunction "2_2") (pintype "passive"))
      (node (ref "U5") (pin "7") (pinfunction "OUT_7") (pintype "output"))
    )
  )
)
